# openSX70_SCHEMATIC_COMPLETE_NEW_LAYOUT_2.net
KiCad netlist of a schematic drawn in EAGLE
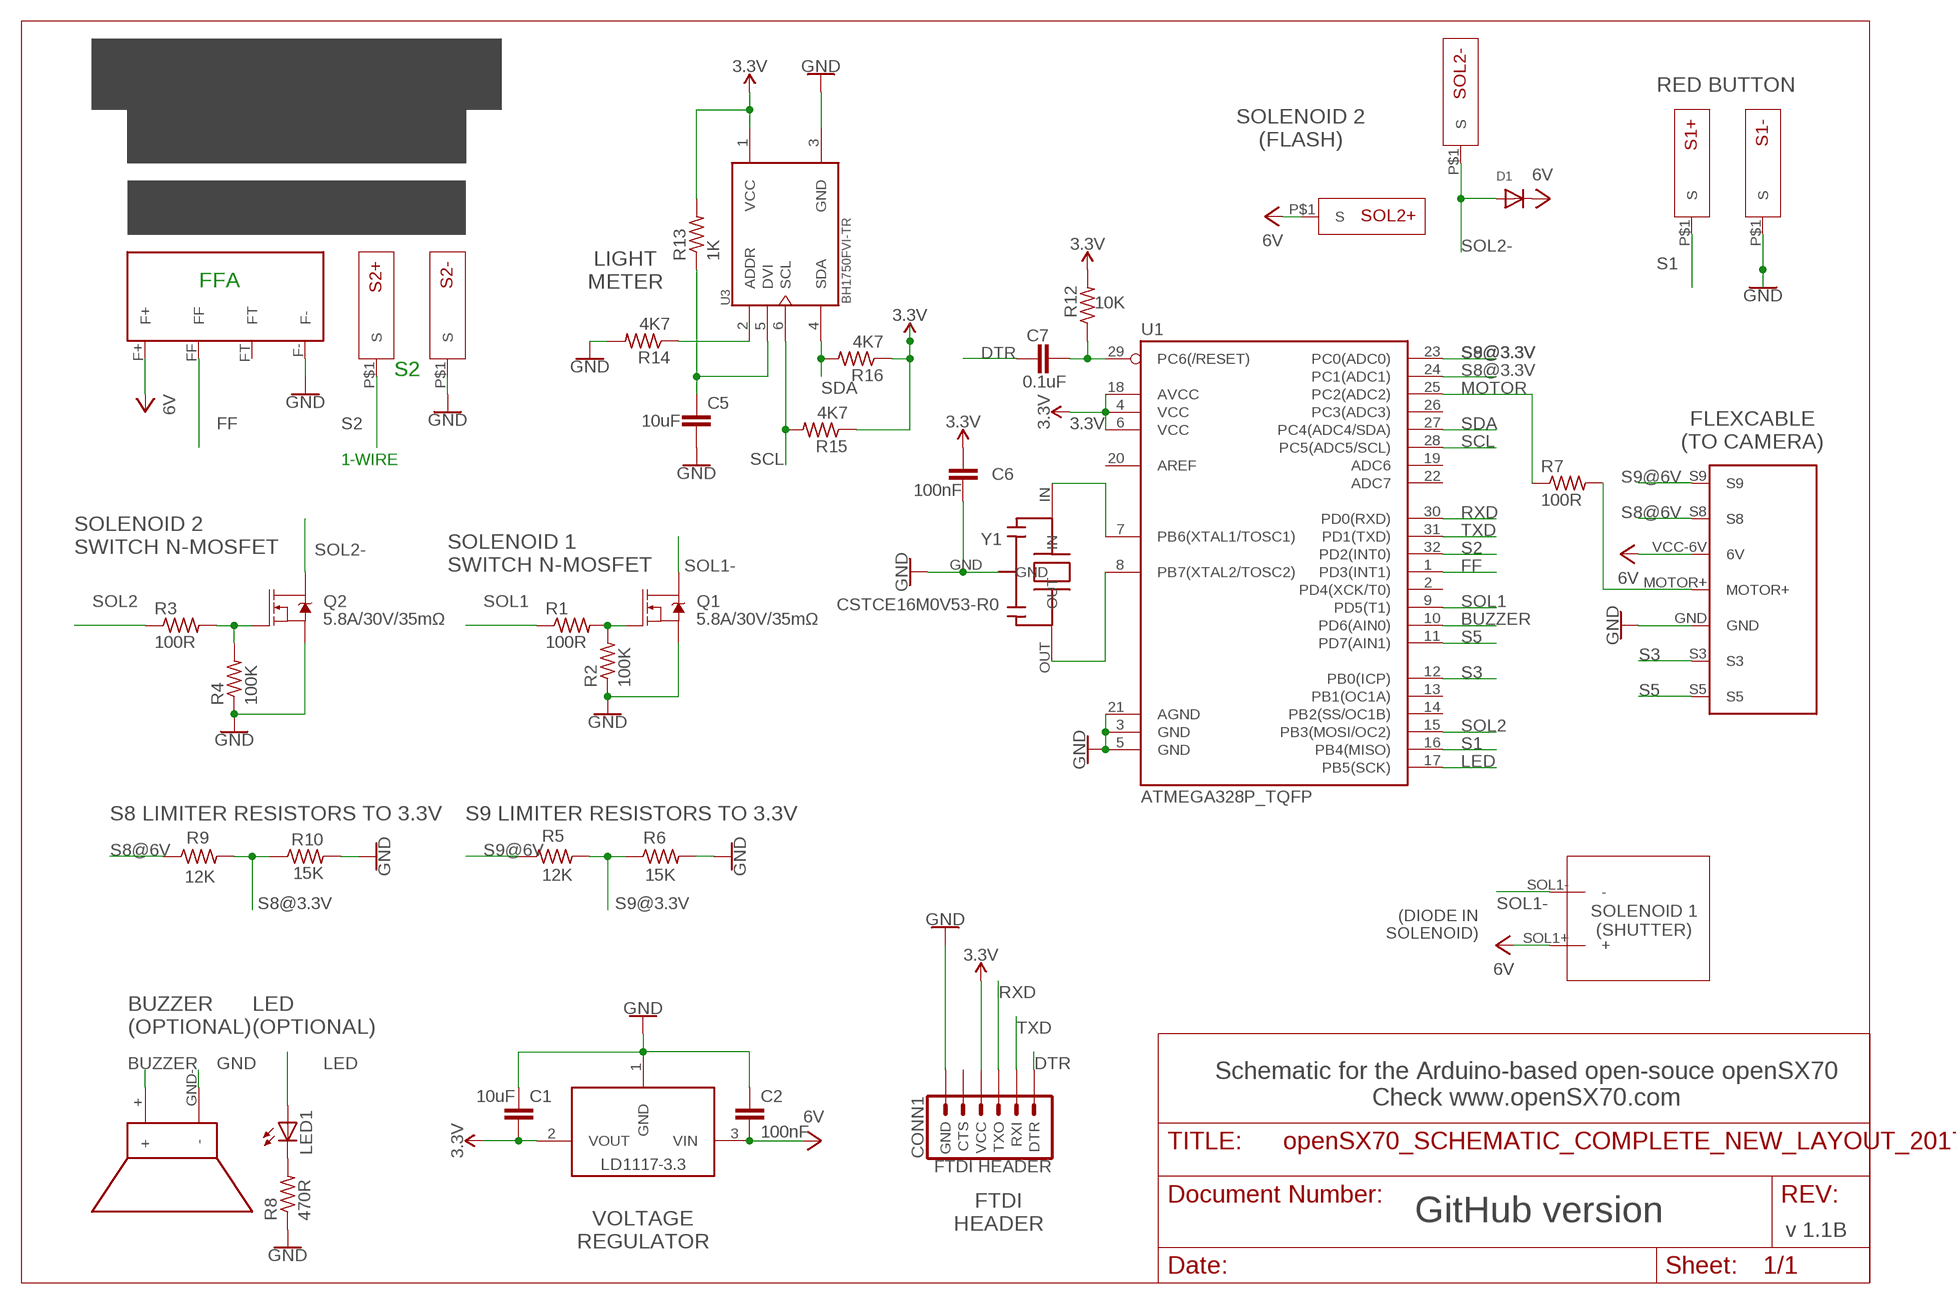
[diagram p0: schematic, sheet 1]

(export (version "E")
  (design (tool "Eeschema 10.0.6"))
  (components
    (comp (ref "BUZZ1")
      (value "CSET8-5G")
      (footprint "eagle-import:CSET8-5G_PACKAGE")
      (libsource (lib "eagle-import") (part "CSET8-5G"))
    )
    (comp (ref "C1")
      (value "10uF")
      (footprint "eagle-import:0603")
      (libsource (lib "eagle-import") (part "10UF-0603-6.3V-20%"))
    )
    (comp (ref "C2")
      (value "100nF")
      (footprint "eagle-import:C0603K")
      (libsource (lib "eagle-import") (part "C-EUC0603K"))
    )
    (comp (ref "C5")
      (value "10uF")
      (footprint "eagle-import:0603")
      (libsource (lib "eagle-import") (part "10UF-0603-6.3V-20%"))
    )
    (comp (ref "C6")
      (value "100nF")
      (footprint "eagle-import:C0805")
      (libsource (lib "eagle-import") (part "resistor_C-EUC0805"))
    )
    (comp (ref "C7")
      (value "0.1uF")
      (footprint "eagle-import:0603")
      (libsource (lib "eagle-import") (part "0.1UF-0603-25V-(+80/-20%)"))
    )
    (comp (ref "CONN1")
      (value "FTDI HEADER")
      (footprint "eagle-import:1X06")
      (libsource (lib "eagle-import") (part "6_PIN_SERIAL_TARGET"))
    )
    (comp (ref "D1")
      (value "DIODESOD-523")
      (footprint "eagle-import:SOD-523")
      (libsource (lib "eagle-import") (part "DIODESOD-523"))
    )
    (comp (ref "LD11173.3V")
      (value "LD1117 3.3V")
      (footprint "eagle-import:SOT223")
      (fields (field (name "MF") "Advanced Monolithic Systems") (field (name "MP") "AMS1117-5.0"))
      (libsource (lib "eagle-import") (part "LD1117-3.3"))
    )
    (comp (ref "LED1")
      (value "LEDCHIPLED_0805")
      (footprint "eagle-import:CHIPLED_0805")
      (libsource (lib "eagle-import") (part "LEDCHIPLED_0805"))
    )
    (comp (ref "Q1")
      (value "5.8A/30V/35mΩ")
      (footprint "eagle-import:SOT23-3")
      (libsource (lib "eagle-import") (part "MOSFET-NCH-AO3404A"))
    )
    (comp (ref "Q2")
      (value "5.8A/30V/35mΩ")
      (footprint "eagle-import:SOT23-3")
      (libsource (lib "eagle-import") (part "MOSFET-NCH-AO3404A"))
    )
    (comp (ref "R1")
      (value "100R")
      (footprint "eagle-import:R0603")
      (libsource (lib "eagle-import") (part "R-US_R0603"))
    )
    (comp (ref "R2")
      (value "100K")
      (footprint "eagle-import:R0603")
      (libsource (lib "eagle-import") (part "R-US_R0603"))
    )
    (comp (ref "R3")
      (value "100R")
      (footprint "eagle-import:R0603")
      (libsource (lib "eagle-import") (part "R-US_R0603"))
    )
    (comp (ref "R4")
      (value "100K")
      (footprint "eagle-import:R0603")
      (libsource (lib "eagle-import") (part "R-US_R0603"))
    )
    (comp (ref "R5")
      (value "12K")
      (footprint "eagle-import:R0603")
      (libsource (lib "eagle-import") (part "R-US_R0603"))
    )
    (comp (ref "R6")
      (value "15K")
      (footprint "eagle-import:R0603")
      (libsource (lib "eagle-import") (part "R-US_R0603"))
    )
    (comp (ref "R7")
      (value "100R")
      (footprint "eagle-import:R0603")
      (libsource (lib "eagle-import") (part "R-US_R0603"))
    )
    (comp (ref "R8")
      (value "470R")
      (footprint "eagle-import:R0603")
      (libsource (lib "eagle-import") (part "R-US_R0603"))
    )
    (comp (ref "R9")
      (value "12K")
      (footprint "eagle-import:R0603")
      (libsource (lib "eagle-import") (part "R-US_R0603"))
    )
    (comp (ref "R10")
      (value "15K")
      (footprint "eagle-import:R0603")
      (libsource (lib "eagle-import") (part "R-US_R0603"))
    )
    (comp (ref "R12")
      (value "10K")
      (footprint "eagle-import:R0603")
      (libsource (lib "eagle-import") (part "R-US_R0603"))
    )
    (comp (ref "R13")
      (value "1K")
      (footprint "eagle-import:R0603")
      (libsource (lib "eagle-import") (part "R-US_R0603"))
    )
    (comp (ref "R14")
      (value "4K7")
      (footprint "eagle-import:R0603")
      (libsource (lib "eagle-import") (part "R-US_R0603"))
    )
    (comp (ref "R15")
      (value "4K7")
      (footprint "eagle-import:R0603")
      (libsource (lib "eagle-import") (part "R-US_R0603"))
    )
    (comp (ref "R16")
      (value "4K7")
      (footprint "eagle-import:R0603")
      (libsource (lib "eagle-import") (part "R-US_R0603"))
    )
    (comp (ref "S1+")
      (value "SX70_S-PAD")
      (footprint "eagle-import:SX70-S-PAD")
      (libsource (lib "eagle-import") (part "SX70_S-PAD"))
    )
    (comp (ref "S1-")
      (value "SX70_S-PAD")
      (footprint "eagle-import:SX70-S-PAD")
      (libsource (lib "eagle-import") (part "SX70_S-PAD"))
    )
    (comp (ref "S2+")
      (value "SX70_S-PAD")
      (footprint "eagle-import:SX70-S-PAD")
      (libsource (lib "eagle-import") (part "SX70_S-PAD"))
    )
    (comp (ref "S2-")
      (value "SX70_S-PAD")
      (footprint "eagle-import:SX70-S-PAD")
      (libsource (lib "eagle-import") (part "SX70_S-PAD"))
    )
    (comp (ref "SOL1")
      (value "SX70-SOLENOID1-2PADS")
      (footprint "eagle-import:SX70-SOLENOID1-2")
      (libsource (lib "eagle-import") (part "SX70-SOLENOID1-2PADS"))
    )
    (comp (ref "SOL2+")
      (value "SX70_S-PAD")
      (footprint "eagle-import:SX70-S-PAD")
      (libsource (lib "eagle-import") (part "SX70_S-PAD"))
    )
    (comp (ref "SOL2-")
      (value "SX70_S-PAD")
      (footprint "eagle-import:SX70-S-PAD")
      (libsource (lib "eagle-import") (part "SX70_S-PAD"))
    )
    (comp (ref "U$1")
      (value "SX70-7-PAD")
      (footprint "eagle-import:SX70-7-PAD")
      (libsource (lib "eagle-import") (part "SX70-7-PAD"))
    )
    (comp (ref "U$2")
      (value "FFA")
      (footprint "eagle-import:FFA-PAD-PACKAGE")
      (libsource (lib "eagle-import") (part "SX70-FFA-PAD"))
    )
    (comp (ref "U1")
      (value "ATMEGA328P_TQFP")
      (footprint "eagle-import:TQFP32-08")
      (libsource (lib "eagle-import") (part "ATMEGA328P_TQFP"))
    )
    (comp (ref "U3")
      (value "BH1750FVI-TR")
      (footprint "eagle-import:SOTFL50P300X75-6N")
      (fields (field (name "MF") "Rohm"))
      (libsource (lib "eagle-import") (part "BH1750FVI-TR"))
    )
    (comp (ref "Y1")
      (value "CSTCE16M0V53-R0")
      (footprint "eagle-import:CFP95P160X100-3N")
      (fields (field (name "MF") "Murata"))
      (libsource (lib "eagle-import") (part "CSTCE16M0V53-R0"))
    )
  )
  (nets
    (net (code "1") (name "/BUZZER") (class "Default")
      (node (ref "BUZZ1") (pin "+") (pinfunction "+_+") (pintype "bidirectional"))
      (node (ref "U1") (pin "10") (pinfunction "PD6(AIN0)_10") (pintype "bidirectional"))
    )
    (net (code "2") (name "/DTR") (class "Default")
      (node (ref "C7") (pin "1") (pinfunction "1_1") (pintype "passive"))
      (node (ref "CONN1") (pin "1") (pinfunction "DTR_1") (pintype "passive"))
    )
    (net (code "3") (name "/FF") (class "Default")
      (node (ref "U$2") (pin "FF") (pinfunction "FF_FF") (pintype "bidirectional"))
      (node (ref "U1") (pin "1") (pinfunction "PD3(INT1)_1") (pintype "bidirectional"))
    )
    (net (code "4") (name "/LED") (class "Default")
      (node (ref "LED1") (pin "A") (pinfunction "A_A") (pintype "passive"))
      (node (ref "U1") (pin "17") (pinfunction "PB5(SCK)_17") (pintype "bidirectional"))
    )
    (net (code "5") (name "/MOTOR") (class "Default")
      (node (ref "R7") (pin "1") (pinfunction "1_1") (pintype "passive"))
      (node (ref "U1") (pin "25") (pinfunction "PC2(ADC2)_25") (pintype "bidirectional"))
    )
    (net (code "6") (name "/RXD") (class "Default")
      (node (ref "CONN1") (pin "3") (pinfunction "TXO_3") (pintype "passive"))
      (node (ref "U1") (pin "30") (pinfunction "PD0(RXD)_30") (pintype "bidirectional"))
    )
    (net (code "7") (name "/S1") (class "Default")
      (node (ref "S1+") (pin "P$1") (pinfunction "S_P$1") (pintype "bidirectional"))
      (node (ref "U1") (pin "16") (pinfunction "PB4(MISO)_16") (pintype "bidirectional"))
    )
    (net (code "8") (name "/S2") (class "Default")
      (node (ref "S2+") (pin "P$1") (pinfunction "S_P$1") (pintype "bidirectional"))
      (node (ref "U1") (pin "32") (pinfunction "PD2(INT0)_32") (pintype "bidirectional"))
    )
    (net (code "9") (name "/S3") (class "Default")
      (node (ref "U$1") (pin "S3") (pinfunction "S3_S3") (pintype "bidirectional"))
      (node (ref "U1") (pin "12") (pinfunction "PB0(ICP)_12") (pintype "bidirectional"))
    )
    (net (code "10") (name "/S5") (class "Default")
      (node (ref "U$1") (pin "S5") (pinfunction "S5_S5") (pintype "bidirectional"))
      (node (ref "U1") (pin "11") (pinfunction "PD7(AIN1)_11") (pintype "bidirectional"))
    )
    (net (code "11") (name "/S8@3.3V") (class "Default")
      (node (ref "R10") (pin "1") (pinfunction "1_1") (pintype "passive"))
      (node (ref "R9") (pin "2") (pinfunction "2_2") (pintype "passive"))
      (node (ref "U1") (pin "24") (pinfunction "PC1(ADC1)_24") (pintype "bidirectional"))
    )
    (net (code "12") (name "/S8@6V") (class "Default")
      (node (ref "R9") (pin "1") (pinfunction "1_1") (pintype "passive"))
      (node (ref "U$1") (pin "S8") (pinfunction "S8_S8") (pintype "bidirectional"))
    )
    (net (code "13") (name "/S9@3.3V") (class "Default")
      (node (ref "R5") (pin "2") (pinfunction "2_2") (pintype "passive"))
      (node (ref "R6") (pin "1") (pinfunction "1_1") (pintype "passive"))
      (node (ref "U1") (pin "23") (pinfunction "PC0(ADC0)_23") (pintype "bidirectional"))
    )
    (net (code "14") (name "/S9@6V") (class "Default")
      (node (ref "R5") (pin "1") (pinfunction "1_1") (pintype "passive"))
      (node (ref "U$1") (pin "S9") (pinfunction "S9_S9") (pintype "bidirectional"))
    )
    (net (code "15") (name "/SCL") (class "Default")
      (node (ref "R15") (pin "2") (pinfunction "2_2") (pintype "passive"))
      (node (ref "U1") (pin "28") (pinfunction "PC5(ADC5/SCL)_28") (pintype "bidirectional"))
      (node (ref "U3") (pin "6") (pinfunction "SCL_6") (pintype "input"))
    )
    (net (code "16") (name "/SDA") (class "Default")
      (node (ref "R16") (pin "2") (pinfunction "2_2") (pintype "passive"))
      (node (ref "U1") (pin "27") (pinfunction "PC4(ADC4/SDA)_27") (pintype "bidirectional"))
      (node (ref "U3") (pin "4") (pinfunction "SDA_4") (pintype "bidirectional"))
    )
    (net (code "17") (name "/SOL1") (class "Default")
      (node (ref "R1") (pin "1") (pinfunction "1_1") (pintype "passive"))
      (node (ref "U1") (pin "9") (pinfunction "PD5(T1)_9") (pintype "bidirectional"))
    )
    (net (code "18") (name "/SOL1-") (class "Default")
      (node (ref "Q1") (pin "3") (pinfunction "D_3") (pintype "bidirectional"))
      (node (ref "SOL1") (pin "SOL1-") (pinfunction "-_SOL1-") (pintype "bidirectional"))
    )
    (net (code "19") (name "/SOL2") (class "Default")
      (node (ref "R3") (pin "1") (pinfunction "1_1") (pintype "passive"))
      (node (ref "U1") (pin "15") (pinfunction "PB3(MOSI/OC2)_15") (pintype "bidirectional"))
    )
    (net (code "20") (name "/SOL2-") (class "Default")
      (node (ref "D1") (pin "A") (pinfunction "A_A") (pintype "passive"))
      (node (ref "Q2") (pin "3") (pinfunction "D_3") (pintype "bidirectional"))
      (node (ref "SOL2-") (pin "P$1") (pinfunction "S_P$1") (pintype "bidirectional"))
    )
    (net (code "21") (name "/TXD") (class "Default")
      (node (ref "CONN1") (pin "2") (pinfunction "RXI_2") (pintype "passive"))
      (node (ref "U1") (pin "31") (pinfunction "PD1(TXD)_31") (pintype "bidirectional"))
    )
    (net (code "22") (name "3.3V") (class "Default")
      (node (ref "C1") (pin "2") (pinfunction "2_2") (pintype "passive"))
      (node (ref "C6") (pin "1") (pinfunction "1_1") (pintype "passive"))
      (node (ref "CONN1") (pin "4") (pinfunction "VCC_4") (pintype "passive"))
      (node (ref "LD11173.3V") (pin "2") (pinfunction "VOUT_2") (pintype "bidirectional"))
      (node (ref "R12") (pin "2") (pinfunction "2_2") (pintype "passive"))
      (node (ref "R13") (pin "2") (pinfunction "2_2") (pintype "passive"))
      (node (ref "R15") (pin "1") (pinfunction "1_1") (pintype "passive"))
      (node (ref "R16") (pin "1") (pinfunction "1_1") (pintype "passive"))
      (node (ref "U1") (pin "18") (pinfunction "AVCC_18") (pintype "bidirectional"))
      (node (ref "U1") (pin "4") (pinfunction "VCC_4") (pintype "bidirectional"))
      (node (ref "U1") (pin "6") (pinfunction "VCC_6") (pintype "bidirectional"))
      (node (ref "U3") (pin "1") (pinfunction "VCC_1") (pintype "power_in"))
    )
    (net (code "23") (name "6V") (class "Default")
      (node (ref "C2") (pin "2") (pinfunction "2_2") (pintype "passive"))
      (node (ref "D1") (pin "K") (pinfunction "C_K") (pintype "passive"))
      (node (ref "LD11173.3V") (pin "3") (pinfunction "VIN_3") (pintype "bidirectional"))
      (node (ref "SOL1") (pin "SOL1+") (pinfunction "+_SOL1+") (pintype "bidirectional"))
      (node (ref "SOL2+") (pin "P$1") (pinfunction "S_P$1") (pintype "bidirectional"))
      (node (ref "U$1") (pin "VCC-6V") (pinfunction "6V_VCC-6V") (pintype "bidirectional"))
      (node (ref "U$2") (pin "F+") (pinfunction "F+_F+") (pintype "bidirectional"))
    )
    (net (code "24") (name "GND") (class "Default")
      (node (ref "BUZZ1") (pin "GND-") (pinfunction "-_GND-") (pintype "bidirectional"))
      (node (ref "C1") (pin "1") (pinfunction "1_1") (pintype "passive"))
      (node (ref "C2") (pin "1") (pinfunction "1_1") (pintype "passive"))
      (node (ref "C5") (pin "2") (pinfunction "2_2") (pintype "passive"))
      (node (ref "C6") (pin "2") (pinfunction "2_2") (pintype "passive"))
      (node (ref "CONN1") (pin "6") (pinfunction "GND_6") (pintype "passive"))
      (node (ref "LD11173.3V") (pin "1") (pinfunction "GND_1") (pintype "bidirectional"))
      (node (ref "Q1") (pin "2") (pinfunction "S_2") (pintype "bidirectional"))
      (node (ref "Q2") (pin "2") (pinfunction "S_2") (pintype "bidirectional"))
      (node (ref "R10") (pin "2") (pinfunction "2_2") (pintype "passive"))
      (node (ref "R14") (pin "2") (pinfunction "2_2") (pintype "passive"))
      (node (ref "R2") (pin "1") (pinfunction "1_1") (pintype "passive"))
      (node (ref "R4") (pin "1") (pinfunction "1_1") (pintype "passive"))
      (node (ref "R6") (pin "2") (pinfunction "2_2") (pintype "passive"))
      (node (ref "R8") (pin "1") (pinfunction "1_1") (pintype "passive"))
      (node (ref "S1-") (pin "P$1") (pinfunction "S_P$1") (pintype "bidirectional"))
      (node (ref "S2-") (pin "P$1") (pinfunction "S_P$1") (pintype "bidirectional"))
      (node (ref "U$1") (pin "GND") (pinfunction "GND_GND") (pintype "bidirectional"))
      (node (ref "U$2") (pin "F-") (pinfunction "F-_F-") (pintype "bidirectional"))
      (node (ref "U1") (pin "21") (pinfunction "AGND_21") (pintype "bidirectional"))
      (node (ref "U1") (pin "3") (pinfunction "GND_3") (pintype "bidirectional"))
      (node (ref "U1") (pin "5") (pinfunction "GND_5") (pintype "bidirectional"))
      (node (ref "U3") (pin "3") (pinfunction "GND_3") (pintype "power_in"))
      (node (ref "Y1") (pin "GND") (pinfunction "GND_GND") (pintype "passive"))
    )
    (net (code "25") (name "Net-(LED1-PadC)") (class "Default")
      (node (ref "LED1") (pin "C") (pinfunction "C_C") (pintype "passive"))
      (node (ref "R8") (pin "2") (pinfunction "2_2") (pintype "passive"))
    )
    (net (code "26") (name "Net-(Q1-G)") (class "Default")
      (node (ref "Q1") (pin "1") (pinfunction "G_1") (pintype "bidirectional"))
      (node (ref "R1") (pin "2") (pinfunction "2_2") (pintype "passive"))
      (node (ref "R2") (pin "2") (pinfunction "2_2") (pintype "passive"))
    )
    (net (code "27") (name "Net-(Q2-G)") (class "Default")
      (node (ref "Q2") (pin "1") (pinfunction "G_1") (pintype "bidirectional"))
      (node (ref "R3") (pin "2") (pinfunction "2_2") (pintype "passive"))
      (node (ref "R4") (pin "2") (pinfunction "2_2") (pintype "passive"))
    )
    (net (code "28") (name "Net-(R7-Pad2)") (class "Default")
      (node (ref "R7") (pin "2") (pinfunction "2_2") (pintype "passive"))
      (node (ref "U$1") (pin "MOTOR+") (pinfunction "MOTOR+_MOTOR+") (pintype "bidirectional"))
    )
    (net (code "29") (name "Net-(U1-PB6(XTAL1{slash}TOSC1))") (class "Default")
      (node (ref "U1") (pin "7") (pinfunction "PB6(XTAL1/TOSC1)_7") (pintype "bidirectional"))
      (node (ref "Y1") (pin "IN") (pinfunction "IN_IN") (pintype "input"))
    )
    (net (code "30") (name "Net-(U1-PB7(XTAL2{slash}TOSC2))") (class "Default")
      (node (ref "U1") (pin "8") (pinfunction "PB7(XTAL2/TOSC2)_8") (pintype "bidirectional"))
      (node (ref "Y1") (pin "OUT") (pinfunction "OUT_OUT") (pintype "output"))
    )
    (net (code "31") (name "Net-(U1-PC6({slash}RESET))") (class "Default")
      (node (ref "C7") (pin "2") (pinfunction "2_2") (pintype "passive"))
      (node (ref "R12") (pin "1") (pinfunction "1_1") (pintype "passive"))
      (node (ref "U1") (pin "29") (pinfunction "PC6(/RESET)_29") (pintype "bidirectional"))
    )
    (net (code "32") (name "Net-(U3-ADDR)") (class "Default")
      (node (ref "R14") (pin "1") (pinfunction "1_1") (pintype "passive"))
      (node (ref "U3") (pin "2") (pinfunction "ADDR_2") (pintype "input"))
    )
    (net (code "33") (name "Net-(U3-DVI)") (class "Default")
      (node (ref "C5") (pin "1") (pinfunction "1_1") (pintype "passive"))
      (node (ref "R13") (pin "1") (pinfunction "1_1") (pintype "passive"))
      (node (ref "U3") (pin "5") (pinfunction "DVI_5") (pintype "input"))
    )
    (net (code "34") (name "unconnected-(CONN1-CTS-Pad5)") (class "Default")
      (node (ref "CONN1") (pin "5") (pinfunction "CTS_5") (pintype "passive"))
    )
    (net (code "35") (name "unconnected-(U$2-PadFT)") (class "Default")
      (node (ref "U$2") (pin "FT") (pinfunction "FT_FT") (pintype "bidirectional"))
    )
    (net (code "36") (name "unconnected-(U1-ADC6-Pad19)") (class "Default")
      (node (ref "U1") (pin "19") (pinfunction "ADC6_19") (pintype "bidirectional"))
    )
    (net (code "37") (name "unconnected-(U1-ADC7-Pad22)") (class "Default")
      (node (ref "U1") (pin "22") (pinfunction "ADC7_22") (pintype "bidirectional"))
    )
    (net (code "38") (name "unconnected-(U1-AREF-Pad20)") (class "Default")
      (node (ref "U1") (pin "20") (pinfunction "AREF_20") (pintype "bidirectional"))
    )
    (net (code "39") (name "unconnected-(U1-PB1(OC1A)-Pad13)") (class "Default")
      (node (ref "U1") (pin "13") (pinfunction "PB1(OC1A)_13") (pintype "bidirectional"))
    )
    (net (code "40") (name "unconnected-(U1-PB2(SS{slash}OC1B)-Pad14)") (class "Default")
      (node (ref "U1") (pin "14") (pinfunction "PB2(SS/OC1B)_14") (pintype "bidirectional"))
    )
    (net (code "41") (name "unconnected-(U1-PC3(ADC3)-Pad26)") (class "Default")
      (node (ref "U1") (pin "26") (pinfunction "PC3(ADC3)_26") (pintype "bidirectional"))
    )
    (net (code "42") (name "unconnected-(U1-PD4(XCK{slash}T0)-Pad2)") (class "Default")
      (node (ref "U1") (pin "2") (pinfunction "PD4(XCK/T0)_2") (pintype "bidirectional"))
    )
  )
)
